# LAN.net
KiCad netlist of a schematic drawn in Altium Designer
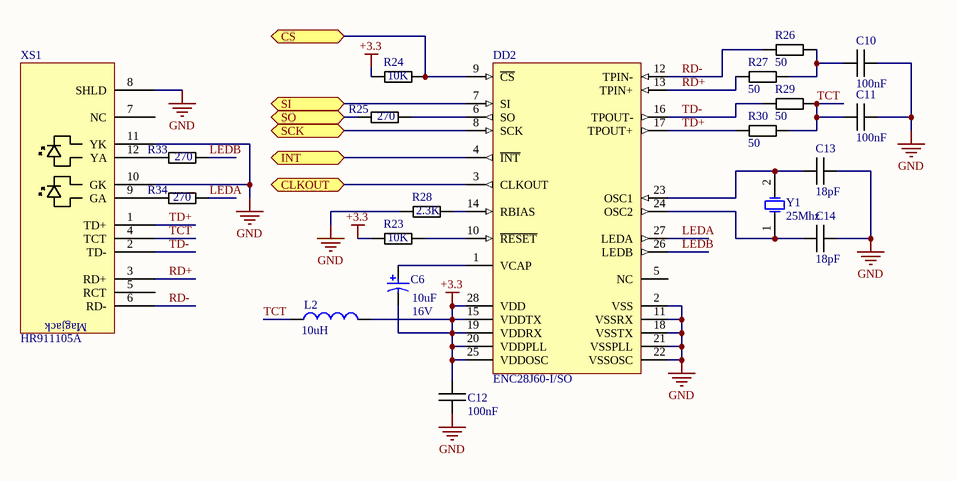
[diagram p0: LAN.SchDoc]

(export (version "E")
  (design (tool "Eeschema 10.0.6"))
  (components
    (comp (ref "C6")
      (value "CAP_Tantalum")
      (footprint "CAP_3530")
      (fields (field (name "CAPACITANCE") "10uF") (field (name "VOLTAGE") "16V"))
      (libsource (lib "altium-import") (part "root_0_CAP_Tantalum_"))
    )
    (comp (ref "C10")
      (value "CAP_SMD")
      (footprint "CAPC1206(3216)170_L")
      (description "Ceramic capacitor, 0805")
      (fields (field (name "VAL") "100nF"))
      (libsource (lib "altium-import") (part "root_0_CAP_SMD_"))
    )
    (comp (ref "C11")
      (value "CAP_SMD")
      (footprint "CAPC1206(3216)170_L")
      (description "Ceramic capacitor, 0805")
      (fields (field (name "VAL") "100nF"))
      (libsource (lib "altium-import") (part "root_0_CAP_SMD_"))
    )
    (comp (ref "C12")
      (value "CAP_SMD")
      (footprint "CAPC1206(3216)170_L")
      (description "Ceramic capacitor, 0805")
      (fields (field (name "VAL") "100nF"))
      (libsource (lib "altium-import") (part "root_1_CAP_SMD_"))
    )
    (comp (ref "C13")
      (value "CAP_SMD")
      (footprint "CAPC1206(3216)170_L")
      (description "Ceramic capacitor, 0805")
      (fields (field (name "VAL") "18pF"))
      (libsource (lib "altium-import") (part "root_0_CAP_SMD_"))
    )
    (comp (ref "C14")
      (value "CAP_SMD")
      (footprint "CAPC1206(3216)170_L")
      (description "Ceramic capacitor, 0805")
      (fields (field (name "VAL") "18pF"))
      (libsource (lib "altium-import") (part "root_0_CAP_SMD_"))
    )
    (comp (ref "DD2")
      (value "ENC28J60-I/SO")
      (footprint "SO-28_M")
      (description "Stand-Alone Ethernet Controller with SPI Interface, 28-Pin SOIC, Industrial Temperature")
      (libsource (lib "web.skorpio") (part "ENC28J60-I/SO"))
    )
    (comp (ref "L2")
      (value "10uH")
      (footprint "IND_1206")
      (description "Inductor")
      (libsource (lib "altium-import") (part "root_0_Inductor_"))
    )
    (comp (ref "R23")
      (value "RES_SMD")
      (footprint "RESC1206(3216)_L")
      (fields (field (name "VAL") "10K"))
      (libsource (lib "altium-import") (part "root_0_RES_SMD_"))
    )
    (comp (ref "R24")
      (value "RES_SMD")
      (footprint "RESC1206(3216)_L")
      (description "RES0805")
      (fields (field (name "VAL") "10K"))
      (libsource (lib "altium-import") (part "root_0_RES_SMD_"))
    )
    (comp (ref "R25")
      (value "RES_SMD")
      (footprint "RESC1206(3216)_L")
      (fields (field (name "VAL") "270"))
      (libsource (lib "altium-import") (part "root_0_RES_SMD_"))
    )
    (comp (ref "R26")
      (value "RES_SMD")
      (footprint "RESC1206(3216)_L")
      (fields (field (name "VAL") "50"))
      (libsource (lib "altium-import") (part "root_0_RES_SMD_"))
    )
    (comp (ref "R27")
      (value "RES_SMD")
      (footprint "RESC1206(3216)_L")
      (fields (field (name "VAL") "50"))
      (libsource (lib "altium-import") (part "root_0_RES_SMD_"))
    )
    (comp (ref "R28")
      (value "RES_SMD")
      (footprint "RESC1206(3216)_L")
      (description "RES0805")
      (fields (field (name "VAL") "2.3K"))
      (libsource (lib "altium-import") (part "root_0_RES_SMD_"))
    )
    (comp (ref "R29")
      (value "RES_SMD")
      (footprint "RESC1206(3216)_L")
      (fields (field (name "VAL") "50"))
      (libsource (lib "altium-import") (part "root_0_RES_SMD_"))
    )
    (comp (ref "R30")
      (value "RES_SMD")
      (footprint "RESC1206(3216)_L")
      (fields (field (name "VAL") "50"))
      (libsource (lib "altium-import") (part "root_0_RES_SMD_"))
    )
    (comp (ref "R33")
      (value "RES_SMD")
      (footprint "RESC1206(3216)_L")
      (description "RES0805")
      (fields (field (name "VAL") "270"))
      (libsource (lib "altium-import") (part "root_0_RES_SMD_"))
    )
    (comp (ref "R34")
      (value "RES_SMD")
      (footprint "RESC1206(3216)_L")
      (description "RES0805")
      (fields (field (name "VAL") "270"))
      (libsource (lib "altium-import") (part "root_0_RES_SMD_"))
    )
    (comp (ref "XS1")
      (value "HR911105A")
      (footprint "HR911105A")
      (libsource (lib "web.skorpio") (part "RJ-45 HR911105A"))
    )
    (comp (ref "Y1")
      (value "25Mhz")
      (footprint "Crystal_SMD")
      (description "Low Profile Crystal")
      (fields (field (name "MANUFACTURER") "ABRACON") (field (name "TOLERANCE") "30PPM"))
      (libsource (lib "altium-import") (part "root_1_Crystal_"))
    )
  )
  (nets
    (net (code "1") (name "+3.3") (class "Default")
      (node (ref "C12") (pin "2") (pinfunction "2_2") (pintype "passive"))
      (node (ref "C6") (pin "2") (pinfunction "2_2") (pintype "passive"))
      (node (ref "DD2") (pin "15") (pinfunction "VDDTX_15") (pintype "power_in"))
      (node (ref "DD2") (pin "19") (pinfunction "VDDRX_19") (pintype "power_in"))
      (node (ref "DD2") (pin "20") (pinfunction "VDDPLL_20") (pintype "power_in"))
      (node (ref "DD2") (pin "25") (pinfunction "VDDOSC_25") (pintype "power_in"))
      (node (ref "DD2") (pin "28") (pinfunction "VDD_28") (pintype "power_in"))
      (node (ref "L2") (pin "2") (pinfunction "2_2") (pintype "passive"))
      (node (ref "R23") (pin "1") (pinfunction "1_1") (pintype "passive"))
      (node (ref "R24") (pin "1") (pinfunction "1_1") (pintype "passive"))
    )
    (net (code "2") (name "/CLKOUT") (class "Default")
      (node (ref "DD2") (pin "3") (pinfunction "CLKOUT_3") (pintype "output"))
    )
    (net (code "3") (name "/CS") (class "Default")
      (node (ref "DD2") (pin "9") (pinfunction "~{CS}_9") (pintype "input"))
      (node (ref "R24") (pin "2") (pinfunction "2_2") (pintype "passive"))
    )
    (net (code "4") (name "/INT") (class "Default")
      (node (ref "DD2") (pin "4") (pinfunction "~{INT}_4") (pintype "output"))
    )
    (net (code "5") (name "/LEDA") (class "Default")
      (node (ref "DD2") (pin "27") (pinfunction "LEDA_27") (pintype "output"))
      (node (ref "R34") (pin "2") (pinfunction "2_2") (pintype "passive"))
    )
    (net (code "6") (name "/LEDB") (class "Default")
      (node (ref "DD2") (pin "26") (pinfunction "LEDB_26") (pintype "output"))
      (node (ref "R33") (pin "2") (pinfunction "2_2") (pintype "passive"))
    )
    (net (code "7") (name "/RD+") (class "Default")
      (node (ref "DD2") (pin "13") (pinfunction "TPIN+_13") (pintype "input"))
      (node (ref "R27") (pin "1") (pinfunction "1_1") (pintype "passive"))
      (node (ref "XS1") (pin "3") (pinfunction "RD+_3") (pintype "passive"))
    )
    (net (code "8") (name "/RD-") (class "Default")
      (node (ref "DD2") (pin "12") (pinfunction "TPIN-_12") (pintype "input"))
      (node (ref "R26") (pin "1") (pinfunction "1_1") (pintype "passive"))
      (node (ref "XS1") (pin "6") (pinfunction "RD-_6") (pintype "passive"))
    )
    (net (code "9") (name "/SCK") (class "Default")
      (node (ref "DD2") (pin "8") (pinfunction "SCK_8") (pintype "input"))
    )
    (net (code "10") (name "/SI") (class "Default")
      (node (ref "DD2") (pin "7") (pinfunction "SI_7") (pintype "input"))
    )
    (net (code "11") (name "/SO") (class "Default")
      (node (ref "R25") (pin "1") (pinfunction "1_1") (pintype "passive"))
    )
    (net (code "12") (name "/TCT") (class "Default")
      (node (ref "C11") (pin "1") (pinfunction "1_1") (pintype "passive"))
      (node (ref "L2") (pin "1") (pinfunction "1_1") (pintype "passive"))
      (node (ref "R29") (pin "2") (pinfunction "2_2") (pintype "passive"))
      (node (ref "R30") (pin "2") (pinfunction "2_2") (pintype "passive"))
      (node (ref "XS1") (pin "4") (pinfunction "TCT_4") (pintype "passive"))
    )
    (net (code "13") (name "/TD+") (class "Default")
      (node (ref "DD2") (pin "17") (pinfunction "TPOUT+_17") (pintype "output"))
      (node (ref "R30") (pin "1") (pinfunction "1_1") (pintype "passive"))
      (node (ref "XS1") (pin "1") (pinfunction "TD+_1") (pintype "passive"))
    )
    (net (code "14") (name "/TD-") (class "Default")
      (node (ref "DD2") (pin "16") (pinfunction "TPOUT-_16") (pintype "output"))
      (node (ref "R29") (pin "1") (pinfunction "1_1") (pintype "passive"))
      (node (ref "XS1") (pin "2") (pinfunction "TD-_2") (pintype "passive"))
    )
    (net (code "15") (name "GND") (class "Default")
      (node (ref "C10") (pin "2") (pinfunction "2_2") (pintype "passive"))
      (node (ref "C11") (pin "2") (pinfunction "2_2") (pintype "passive"))
      (node (ref "C12") (pin "1") (pinfunction "1_1") (pintype "passive"))
      (node (ref "C13") (pin "2") (pinfunction "2_2") (pintype "passive"))
      (node (ref "C14") (pin "2") (pinfunction "2_2") (pintype "passive"))
      (node (ref "DD2") (pin "11") (pinfunction "VSSRX_11") (pintype "power_in"))
      (node (ref "DD2") (pin "18") (pinfunction "VSSTX_18") (pintype "power_in"))
      (node (ref "DD2") (pin "2") (pinfunction "VSS_2") (pintype "power_in"))
      (node (ref "DD2") (pin "21") (pinfunction "VSSPLL_21") (pintype "power_in"))
      (node (ref "DD2") (pin "22") (pinfunction "VSSOSC_22") (pintype "power_in"))
      (node (ref "R28") (pin "1") (pinfunction "1_1") (pintype "passive"))
      (node (ref "XS1") (pin "10") (pinfunction "GK_10") (pintype "passive"))
      (node (ref "XS1") (pin "11") (pinfunction "YK_11") (pintype "passive"))
      (node (ref "XS1") (pin "8") (pinfunction "SHLD_8") (pintype "passive"))
    )
    (net (code "16") (name "Net-(C10-Pad1)") (class "Default")
      (node (ref "C10") (pin "1") (pinfunction "1_1") (pintype "passive"))
      (node (ref "R26") (pin "2") (pinfunction "2_2") (pintype "passive"))
      (node (ref "R27") (pin "2") (pinfunction "2_2") (pintype "passive"))
    )
    (net (code "17") (name "Net-(DD2-OSC1)") (class "Default")
      (node (ref "C13") (pin "1") (pinfunction "1_1") (pintype "passive"))
      (node (ref "DD2") (pin "23") (pinfunction "OSC1_23") (pintype "input"))
      (node (ref "Y1") (pin "2") (pinfunction "X2_2") (pintype "passive"))
    )
    (net (code "18") (name "Net-(DD2-OSC2)") (class "Default")
      (node (ref "C14") (pin "1") (pinfunction "1_1") (pintype "passive"))
      (node (ref "DD2") (pin "24") (pinfunction "OSC2_24") (pintype "output"))
      (node (ref "Y1") (pin "1") (pinfunction "X1_1") (pintype "passive"))
    )
    (net (code "19") (name "Net-(DD2-RBIAS)") (class "Default")
      (node (ref "DD2") (pin "14") (pinfunction "RBIAS_14") (pintype "input"))
      (node (ref "R28") (pin "2") (pinfunction "2_2") (pintype "passive"))
    )
    (net (code "20") (name "Net-(DD2-SO)") (class "Default")
      (node (ref "DD2") (pin "6") (pinfunction "SO_6") (pintype "output"))
      (node (ref "R25") (pin "2") (pinfunction "2_2") (pintype "passive"))
    )
    (net (code "21") (name "Net-(DD2-VCAP)") (class "Default")
      (node (ref "C6") (pin "1") (pinfunction "1_1") (pintype "passive"))
      (node (ref "DD2") (pin "1") (pinfunction "VCAP_1") (pintype "power_in"))
    )
    (net (code "22") (name "Net-(DD2-~{RESET})") (class "Default")
      (node (ref "DD2") (pin "10") (pinfunction "~{RESET}_10") (pintype "input"))
      (node (ref "R23") (pin "2") (pinfunction "2_2") (pintype "passive"))
    )
    (net (code "23") (name "Net-(XS1-GA)") (class "Default")
      (node (ref "R34") (pin "1") (pinfunction "1_1") (pintype "passive"))
      (node (ref "XS1") (pin "9") (pinfunction "GA_9") (pintype "passive"))
    )
    (net (code "24") (name "Net-(XS1-YA)") (class "Default")
      (node (ref "R33") (pin "1") (pinfunction "1_1") (pintype "passive"))
      (node (ref "XS1") (pin "12") (pinfunction "YA_12") (pintype "passive"))
    )
    (net (code "25") (name "unconnected-(DD2-NC-Pad5)") (class "Default")
      (node (ref "DD2") (pin "5") (pinfunction "NC_5") (pintype "passive"))
    )
    (net (code "26") (name "unconnected-(XS1-NC-Pad7)") (class "Default")
      (node (ref "XS1") (pin "7") (pinfunction "NC_7") (pintype "passive"))
    )
    (net (code "27") (name "unconnected-(XS1-RCT-Pad5)") (class "Default")
      (node (ref "XS1") (pin "5") (pinfunction "RCT_5") (pintype "passive"))
    )
  )
)
